# Thing_Plus_MGM240P.net
KiCad netlist of a schematic drawn in EAGLE
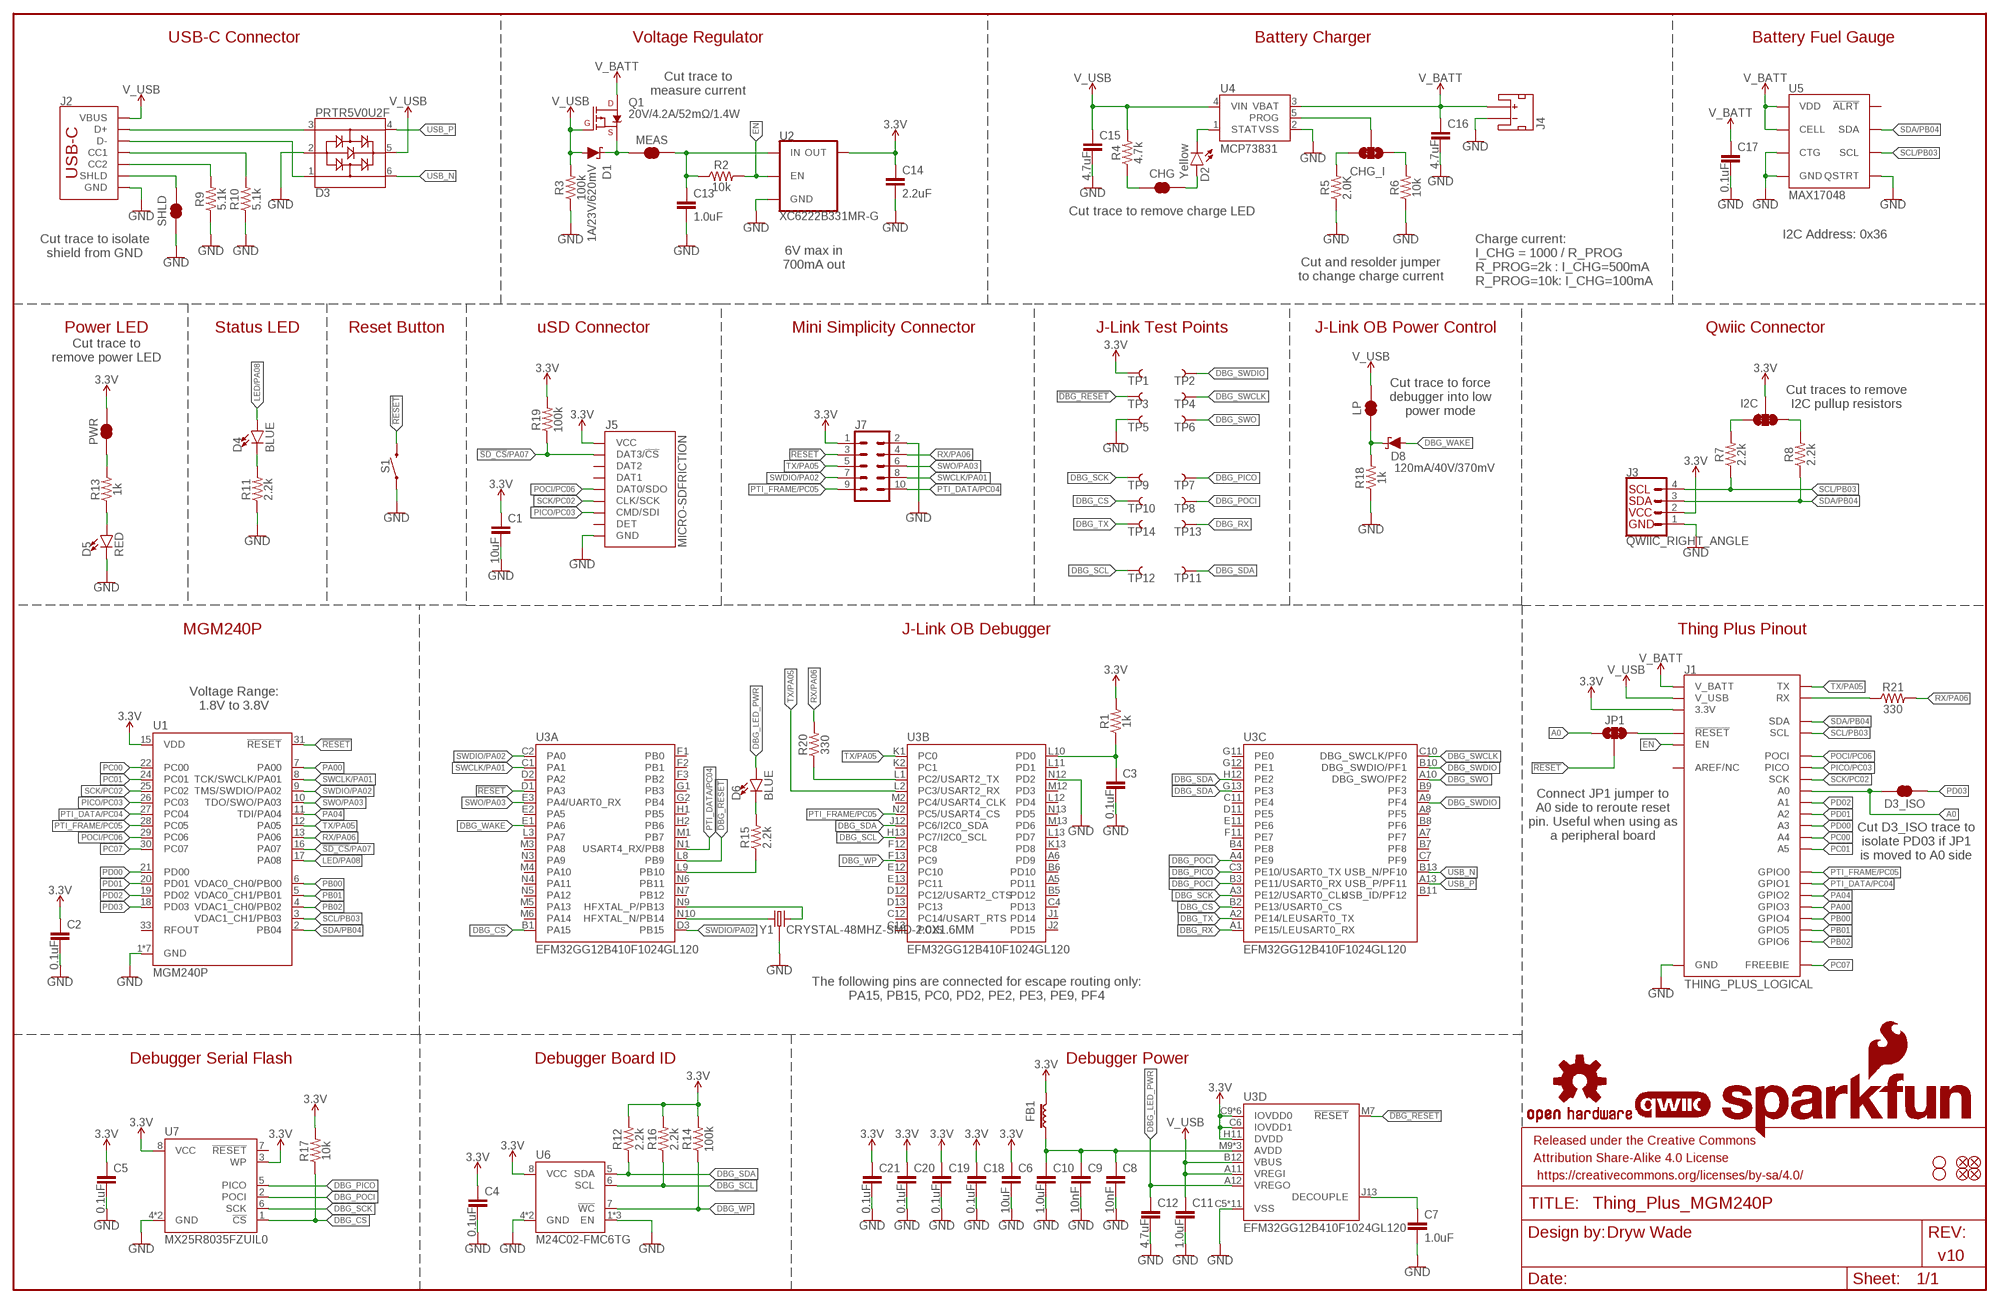
[diagram p0: schematic, sheet 1]

(export (version "E")
  (design (tool "Eeschema 10.0.6"))
  (components
    (comp (ref "C1")
      (value "10uF")
      (footprint "eagle-import:0402-TIGHT")
      (libsource (lib "eagle-import") (part "10UF-0402T-6.3V-20%"))
    )
    (comp (ref "C2")
      (value "0.1uF")
      (footprint "eagle-import:0402-TIGHT")
      (libsource (lib "eagle-import") (part "0.1UF-0402T-6.3V-10%-X7R"))
    )
    (comp (ref "C3")
      (value "0.1uF")
      (footprint "eagle-import:0402-TIGHT")
      (libsource (lib "eagle-import") (part "0.1UF-0402T-6.3V-10%-X7R"))
    )
    (comp (ref "C4")
      (value "0.1uF")
      (footprint "eagle-import:0402-TIGHT")
      (libsource (lib "eagle-import") (part "0.1UF-0402T-6.3V-10%-X7R"))
    )
    (comp (ref "C5")
      (value "0.1uF")
      (footprint "eagle-import:0402-TIGHT")
      (libsource (lib "eagle-import") (part "0.1UF-0402T-6.3V-10%-X7R"))
    )
    (comp (ref "C6")
      (value "10uF")
      (footprint "eagle-import:0402-TIGHT")
      (libsource (lib "eagle-import") (part "10UF-0402T-6.3V-20%"))
    )
    (comp (ref "C7")
      (value "1.0uF")
      (footprint "eagle-import:0603")
      (libsource (lib "eagle-import") (part "1.0UF-0603-16V-10%-X7R"))
    )
    (comp (ref "C8")
      (value "10nF")
      (footprint "eagle-import:0402-TIGHT")
      (libsource (lib "eagle-import") (part "10NF-0402T-25V-10%"))
    )
    (comp (ref "C9")
      (value "10nF")
      (footprint "eagle-import:0402-TIGHT")
      (libsource (lib "eagle-import") (part "10NF-0402T-25V-10%"))
    )
    (comp (ref "C10")
      (value "1.0uF")
      (footprint "eagle-import:0402-TIGHT")
      (libsource (lib "eagle-import") (part "1.0UF-0402T-16V-10%"))
    )
    (comp (ref "C11")
      (value "1.0uF")
      (footprint "eagle-import:0402-TIGHT")
      (libsource (lib "eagle-import") (part "1.0UF-0402T-16V-10%"))
    )
    (comp (ref "C12")
      (value "4.7uF")
      (footprint "eagle-import:0402-TIGHT")
      (libsource (lib "eagle-import") (part "4.7UF-0402_TIGHT-6.3V-20%-X5R"))
    )
    (comp (ref "C13")
      (value "1.0uF")
      (footprint "eagle-import:0402-TIGHT")
      (libsource (lib "eagle-import") (part "1.0UF-0402T-16V-10%"))
    )
    (comp (ref "C14")
      (value "2.2uF")
      (footprint "eagle-import:0402-TIGHT")
      (libsource (lib "eagle-import") (part "2.2UF-0402_TIGHT-10V-10%-X5R"))
    )
    (comp (ref "C15")
      (value "4.7uF")
      (footprint "eagle-import:0402-TIGHT")
      (libsource (lib "eagle-import") (part "4.7UF-0402_TIGHT-6.3V-20%-X5R"))
    )
    (comp (ref "C16")
      (value "4.7uF")
      (footprint "eagle-import:0402-TIGHT")
      (libsource (lib "eagle-import") (part "4.7UF-0402_TIGHT-6.3V-20%-X5R"))
    )
    (comp (ref "C17")
      (value "0.1uF")
      (footprint "eagle-import:0402-TIGHT")
      (libsource (lib "eagle-import") (part "0.1UF-0402T-6.3V-10%-X7R"))
    )
    (comp (ref "C18")
      (value "0.1uF")
      (footprint "eagle-import:0402-TIGHT")
      (libsource (lib "eagle-import") (part "0.1UF-0402T-6.3V-10%-X7R"))
    )
    (comp (ref "C19")
      (value "0.1uF")
      (footprint "eagle-import:0402-TIGHT")
      (libsource (lib "eagle-import") (part "0.1UF-0402T-6.3V-10%-X7R"))
    )
    (comp (ref "C20")
      (value "0.1uF")
      (footprint "eagle-import:0402-TIGHT")
      (libsource (lib "eagle-import") (part "0.1UF-0402T-6.3V-10%-X7R"))
    )
    (comp (ref "C21")
      (value "0.1uF")
      (footprint "eagle-import:0402-TIGHT")
      (libsource (lib "eagle-import") (part "0.1UF-0402T-6.3V-10%-X7R"))
    )
    (comp (ref "CHG")
      (value "JUMPER-SMT_2_NC_TRACE_SILK")
      (footprint "eagle-import:SMT-JUMPER_2_NC_TRACE_SILK")
      (libsource (lib "eagle-import") (part "JUMPER-SMT_2_NC_TRACE_SILK"))
    )
    (comp (ref "CHG_I")
      (value "JUMPER-SMT_3_1-NC_TRACE_SILK")
      (footprint "eagle-import:SMT-JUMPER_3_1-NC_TRACE_SILK")
      (libsource (lib "eagle-import") (part "JUMPER-SMT_3_1-NC_TRACE_SILK"))
    )
    (comp (ref "D1")
      (value "1A/23V/620mV")
      (footprint "eagle-import:SOD-323")
      (libsource (lib "eagle-import") (part "DIODE-SCHOTTKY-BAT20J"))
    )
    (comp (ref "D2")
      (value "Yellow")
      (footprint "eagle-import:LED-0603")
      (libsource (lib "eagle-import") (part "LED-YELLOW0603"))
    )
    (comp (ref "D3")
      (value "PRTR5V0U2F")
      (footprint "eagle-import:SOT886")
      (libsource (lib "eagle-import") (part "PRTR5V0U2F"))
    )
    (comp (ref "D3_ISO")
      (value "JUMPER-SMT_2_NC_TRACE_SILK")
      (footprint "eagle-import:SMT-JUMPER_2_NC_TRACE_SILK")
      (libsource (lib "eagle-import") (part "JUMPER-SMT_2_NC_TRACE_SILK"))
    )
    (comp (ref "D4")
      (value "BLUE")
      (footprint "eagle-import:LED-0603")
      (libsource (lib "eagle-import") (part "LED-BLUE0603"))
    )
    (comp (ref "D5")
      (value "RED")
      (footprint "eagle-import:LED-0603")
      (libsource (lib "eagle-import") (part "LED-RED0603"))
    )
    (comp (ref "D6")
      (value "BLUE")
      (footprint "eagle-import:LED-0603")
      (libsource (lib "eagle-import") (part "LED-BLUE0603"))
    )
    (comp (ref "D8")
      (value "120mA/40V/370mV")
      (footprint "eagle-import:SOD-523")
      (libsource (lib "eagle-import") (part "DIODE-SCHOTTKY-RB751S40"))
    )
    (comp (ref "FB1")
      (value "FERRITE_BEAD-120_OHM-0402T")
      (footprint "eagle-import:0402-TIGHT")
      (libsource (lib "eagle-import") (part "FERRITE_BEAD-120_OHM-0402T"))
    )
    (comp (ref "FD1")
      (value "FIDUCIAL1X2")
      (footprint "eagle-import:FIDUCIAL-1X2")
      (libsource (lib "eagle-import") (part "FIDUCIAL1X2"))
    )
    (comp (ref "FD2")
      (value "FIDUCIAL1X2")
      (footprint "eagle-import:FIDUCIAL-1X2")
      (libsource (lib "eagle-import") (part "FIDUCIAL1X2"))
    )
    (comp (ref "FD3")
      (value "FIDUCIAL1X2")
      (footprint "eagle-import:FIDUCIAL-1X2")
      (libsource (lib "eagle-import") (part "FIDUCIAL1X2"))
    )
    (comp (ref "FD4")
      (value "FIDUCIAL1X2")
      (footprint "eagle-import:FIDUCIAL-1X2")
      (libsource (lib "eagle-import") (part "FIDUCIAL1X2"))
    )
    (comp (ref "FRAME1")
      (value "FRAME-LEDGER")
      (footprint "eagle-import:CREATIVE_COMMONS")
      (libsource (lib "eagle-import") (part "FRAME-LEDGER"))
    )
    (comp (ref "H1")
      (value "STAND-OFF")
      (footprint "eagle-import:STAND-OFF")
      (libsource (lib "eagle-import") (part "STAND-OFF"))
    )
    (comp (ref "H2")
      (value "STAND-OFF")
      (footprint "eagle-import:STAND-OFF")
      (libsource (lib "eagle-import") (part "STAND-OFF"))
    )
    (comp (ref "I2C")
      (value "JUMPER-SMT_3_2-NC_TRACE_SILK")
      (footprint "eagle-import:SMT-JUMPER_3_2-NC_TRACE_SILK")
      (libsource (lib "eagle-import") (part "JUMPER-SMT_3_2-NC_TRACE_SILK"))
    )
    (comp (ref "J1")
      (value "THING_PLUS_LOGICAL")
      (footprint "eagle-import:THING_PLUS")
      (libsource (lib "eagle-import") (part "THING_PLUS_LOGICAL"))
    )
    (comp (ref "J2")
      (value "USB Female Type C Connector")
      (footprint "eagle-import:USB-C-16P-4LAYER-ISOLATED")
      (libsource (lib "eagle-import") (part "USB_C_4-LAYER-ISOLATED"))
    )
    (comp (ref "J3")
      (value "QWIIC_RIGHT_ANGLE")
      (footprint "eagle-import:JST04_1MM_RA")
      (libsource (lib "eagle-import") (part "QWIIC_CONNECTORJS-1MM"))
    )
    (comp (ref "J4")
      (value "JST_2MM_MALE")
      (footprint "eagle-import:JST-2-SMD")
      (libsource (lib "eagle-import") (part "JST_2MM_MALE"))
    )
    (comp (ref "J5")
      (value "MICRO-SDFRICTION")
      (footprint "eagle-import:MICROSD_TINY")
      (libsource (lib "eagle-import") (part "MICRO-SDFRICTION"))
    )
    (comp (ref "J7")
      (value "CONN_05X20.05_IN_PTH_SILK")
      (footprint "eagle-import:2X5_PTH_SILK_.05")
      (libsource (lib "eagle-import") (part "CONN_05X20.05_IN_PTH_SILK"))
    )
    (comp (ref "JP1")
      (value "JUMPER-SMT_3_1-NC_TRACE_SILK")
      (footprint "eagle-import:SMT-JUMPER_3_1-NC_TRACE_SILK")
      (libsource (lib "eagle-import") (part "JUMPER-SMT_3_1-NC_TRACE_SILK"))
    )
    (comp (ref "LOGO1")
      (value "SFE_LOGO_NAME_FLAME.1_INCH")
      (footprint "eagle-import:SFE_LOGO_NAME_FLAME_.1")
      (libsource (lib "eagle-import") (part "SFE_LOGO_NAME_FLAME.1_INCH"))
    )
    (comp (ref "LOGO2")
      (value "QWIIC_LOGO_3MM")
      (footprint "eagle-import:QWIIC_3MM")
      (libsource (lib "eagle-import") (part "QWIIC_LOGO_3MM"))
    )
    (comp (ref "LOGO3")
      (value "OSHW-LOGOS")
      (footprint "eagle-import:OSHW-LOGO-S")
      (libsource (lib "eagle-import") (part "OSHW-LOGOS"))
    )
    (comp (ref "LP")
      (value "JUMPER-SMT_2_NC_TRACE_SILK")
      (footprint "eagle-import:SMT-JUMPER_2_NC_TRACE_SILK")
      (libsource (lib "eagle-import") (part "JUMPER-SMT_2_NC_TRACE_SILK"))
    )
    (comp (ref "MEAS")
      (value "JUMPER-COMBO_2_NC_TRACE")
      (footprint "eagle-import:COMBO-JUMPER_2_NC_TRACE")
      (libsource (lib "eagle-import") (part "JUMPER-COMBO_2_NC_TRACE"))
    )
    (comp (ref "PWR")
      (value "JUMPER-SMT_2_NC_TRACE_SILK")
      (footprint "eagle-import:SMT-JUMPER_2_NC_TRACE_SILK")
      (libsource (lib "eagle-import") (part "JUMPER-SMT_2_NC_TRACE_SILK"))
    )
    (comp (ref "Q1")
      (value "20V/4.2A/52mΩ/1.4W")
      (footprint "eagle-import:SOT23-3")
      (libsource (lib "eagle-import") (part "MOSFET_PCH-DMG2305UX-7"))
    )
    (comp (ref "R1")
      (value "1k")
      (footprint "eagle-import:0402-TIGHT")
      (libsource (lib "eagle-import") (part "1KOHM-0402T-1/16W-1%"))
    )
    (comp (ref "R2")
      (value "10k")
      (footprint "eagle-import:0402-TIGHT")
      (libsource (lib "eagle-import") (part "10KOHM-0402T-1/16W-1%"))
    )
    (comp (ref "R3")
      (value "100k")
      (footprint "eagle-import:0402-TIGHT")
      (libsource (lib "eagle-import") (part "100KOHM-0402T-1/16W-1%"))
    )
    (comp (ref "R4")
      (value "4.7k")
      (footprint "eagle-import:0402-TIGHT")
      (libsource (lib "eagle-import") (part "4.7KOHM-0402T-1/16W-1%"))
    )
    (comp (ref "R5")
      (value "2.0K")
      (footprint "eagle-import:0402-TIGHT")
      (libsource (lib "eagle-import") (part "2.0KOHM-0402T-1/16W-1%"))
    )
    (comp (ref "R6")
      (value "10k")
      (footprint "eagle-import:0402-TIGHT")
      (libsource (lib "eagle-import") (part "10KOHM-0402T-1/16W-1%"))
    )
    (comp (ref "R7")
      (value "2.2k")
      (footprint "eagle-import:0402-TIGHT")
      (libsource (lib "eagle-import") (part "2.2KOHM-0402T-1/16W-1%"))
    )
    (comp (ref "R8")
      (value "2.2k")
      (footprint "eagle-import:0402-TIGHT")
      (libsource (lib "eagle-import") (part "2.2KOHM-0402T-1/16W-1%"))
    )
    (comp (ref "R9")
      (value "5.1k")
      (footprint "eagle-import:0402-TIGHT")
      (libsource (lib "eagle-import") (part "5.1KOHM-0402T-1/16W-1%"))
    )
    (comp (ref "R10")
      (value "5.1k")
      (footprint "eagle-import:0402-TIGHT")
      (libsource (lib "eagle-import") (part "5.1KOHM-0402T-1/16W-1%"))
    )
    (comp (ref "R11")
      (value "2.2k")
      (footprint "eagle-import:0402-TIGHT")
      (libsource (lib "eagle-import") (part "2.2KOHM-0402T-1/16W-1%"))
    )
    (comp (ref "R12")
      (value "2.2k")
      (footprint "eagle-import:0402-TIGHT")
      (libsource (lib "eagle-import") (part "2.2KOHM-0402T-1/16W-1%"))
    )
    (comp (ref "R13")
      (value "1k")
      (footprint "eagle-import:0402-TIGHT")
      (libsource (lib "eagle-import") (part "1KOHM-0402T-1/16W-1%"))
    )
    (comp (ref "R14")
      (value "100k")
      (footprint "eagle-import:0402-TIGHT")
      (libsource (lib "eagle-import") (part "100KOHM-0402T-1/16W-1%"))
    )
    (comp (ref "R15")
      (value "2.2k")
      (footprint "eagle-import:0402-TIGHT")
      (libsource (lib "eagle-import") (part "2.2KOHM-0402T-1/16W-1%"))
    )
    (comp (ref "R16")
      (value "2.2k")
      (footprint "eagle-import:0402-TIGHT")
      (libsource (lib "eagle-import") (part "2.2KOHM-0402T-1/16W-1%"))
    )
    (comp (ref "R17")
      (value "10k")
      (footprint "eagle-import:0402-TIGHT")
      (libsource (lib "eagle-import") (part "10KOHM-0402T-1/16W-1%"))
    )
    (comp (ref "R18")
      (value "1k")
      (footprint "eagle-import:0402-TIGHT")
      (libsource (lib "eagle-import") (part "1KOHM-0402T-1/16W-1%"))
    )
    (comp (ref "R19")
      (value "100k")
      (footprint "eagle-import:0402-TIGHT")
      (libsource (lib "eagle-import") (part "100KOHM-0402T-1/16W-1%"))
    )
    (comp (ref "R20")
      (value "330")
      (footprint "eagle-import:0402-TIGHT")
      (libsource (lib "eagle-import") (part "330OHM-0402T-1/16W-5%"))
    )
    (comp (ref "R21")
      (value "330")
      (footprint "eagle-import:0402-TIGHT")
      (libsource (lib "eagle-import") (part "330OHM-0402T-1/16W-5%"))
    )
    (comp (ref "S1")
      (value "MOMENTARY-SWITCH-SPST-SMD-4.6X2.8MM")
      (footprint "eagle-import:TACTILE_SWITCH_SMD_4.6X2.8MM")
      (libsource (lib "eagle-import") (part "MOMENTARY-SWITCH-SPST-SMD-4.6X2.8MM"))
    )
    (comp (ref "SHLD")
      (value "JUMPER-SMT_2_NC_TRACE_SILK")
      (footprint "eagle-import:SMT-JUMPER_2_NC_TRACE_SILK")
      (libsource (lib "eagle-import") (part "JUMPER-SMT_2_NC_TRACE_SILK"))
    )
    (comp (ref "TP1")
      (value "TEST-POINT3")
      (footprint "eagle-import:PAD.03X.03")
      (libsource (lib "eagle-import") (part "TEST-POINT3"))
    )
    (comp (ref "TP2")
      (value "TEST-POINT3")
      (footprint "eagle-import:PAD.03X.03")
      (libsource (lib "eagle-import") (part "TEST-POINT3"))
    )
    (comp (ref "TP3")
      (value "TEST-POINT3")
      (footprint "eagle-import:PAD.03X.03")
      (libsource (lib "eagle-import") (part "TEST-POINT3"))
    )
    (comp (ref "TP4")
      (value "TEST-POINT3")
      (footprint "eagle-import:PAD.03X.03")
      (libsource (lib "eagle-import") (part "TEST-POINT3"))
    )
    (comp (ref "TP5")
      (value "TEST-POINT3")
      (footprint "eagle-import:PAD.03X.03")
      (libsource (lib "eagle-import") (part "TEST-POINT3"))
    )
    (comp (ref "TP6")
      (value "TEST-POINT3")
      (footprint "eagle-import:PAD.03X.03")
      (libsource (lib "eagle-import") (part "TEST-POINT3"))
    )
    (comp (ref "TP7")
      (value "TEST-POINT3")
      (footprint "eagle-import:PAD.03X.03")
      (libsource (lib "eagle-import") (part "TEST-POINT3"))
    )
    (comp (ref "TP8")
      (value "TEST-POINT3")
      (footprint "eagle-import:PAD.03X.03")
      (libsource (lib "eagle-import") (part "TEST-POINT3"))
    )
    (comp (ref "TP9")
      (value "TEST-POINT3")
      (footprint "eagle-import:PAD.03X.03")
      (libsource (lib "eagle-import") (part "TEST-POINT3"))
    )
    (comp (ref "TP10")
      (value "TEST-POINT3")
      (footprint "eagle-import:PAD.03X.03")
      (libsource (lib "eagle-import") (part "TEST-POINT3"))
    )
    (comp (ref "TP11")
      (value "TEST-POINT3")
      (footprint "eagle-import:PAD.03X.03")
      (libsource (lib "eagle-import") (part "TEST-POINT3"))
    )
    (comp (ref "TP12")
      (value "TEST-POINT3")
      (footprint "eagle-import:PAD.03X.03")
      (libsource (lib "eagle-import") (part "TEST-POINT3"))
    )
    (comp (ref "TP13")
      (value "TEST-POINT3")
      (footprint "eagle-import:PAD.03X.03")
      (libsource (lib "eagle-import") (part "TEST-POINT3"))
    )
    (comp (ref "TP14")
      (value "TEST-POINT3")
      (footprint "eagle-import:PAD.03X.03")
      (libsource (lib "eagle-import") (part "TEST-POINT3"))
    )
    (comp (ref "U1")
      (value "MGM240P")
      (footprint "eagle-import:MGM240P")
      (libsource (lib "eagle-import") (part "MGM240P"))
    )
    (comp (ref "U2")
      (value "XC6222B331MR-G")
      (footprint "eagle-import:SOT23-5")
      (libsource (lib "eagle-import") (part "XC6222B331MR-G"))
    )
    (comp (ref "U3")
      (value "EFM32GG12B410F1024GL120")
      (footprint "eagle-import:BGA120")
      (libsource (lib "eagle-import") (part "EFM32GG12B410F1024GL120"))
    )
    (comp (ref "U4")
      (value "MCP73831")
      (footprint "eagle-import:SOT23-5")
      (libsource (lib "eagle-import") (part "MCP73831"))
    )
    (comp (ref "U5")
      (value "MAX17048")
      (footprint "eagle-import:DFN-8")
      (libsource (lib "eagle-import") (part "MAX17048DFN8"))
    )
    (comp (ref "U6")
      (value "M24C02-FMC6TG")
      (footprint "eagle-import:DFN8_2X3MM")
      (libsource (lib "eagle-import") (part "M24C02-FMC6TG"))
    )
    (comp (ref "U7")
      (value "MX25R8035FZUIL0")
      (footprint "eagle-import:USON-8_2X3MM")
      (libsource (lib "eagle-import") (part "MX25R8035FZUIL0"))
    )
    (comp (ref "Y1")
      (value "CRYSTAL-48MHZ-SMD-2.0X1.6MM")
      (footprint "eagle-import:CRYSTAL-SMD-2.0X1.6MM-ECS")
      (libsource (lib "eagle-import") (part "CRYSTAL-48MHZ-SMD-2.0X1.6MM"))
    )
  )
  (nets
    (net (code "1") (name "/~{DBG_RESET}") (class "Default")
      (node (ref "TP3") (pin "1") (pinfunction "1_1") (pintype "bidirectional"))
      (node (ref "U3") (pin "L8") (pinfunction "PB9_L8") (pintype "bidirectional"))
      (node (ref "U3") (pin "M7") (pinfunction "~{RESET}_M7") (pintype "bidirectional"))
    )
    (net (code "2") (name "/~{RESET}") (class "Default")
      (node (ref "J7") (pin "3") (pinfunction "3_3") (pintype "passive"))
      (node (ref "JP1") (pin "2") (pinfunction "2_2") (pintype "passive"))
      (node (ref "S1") (pin "3") (pinfunction "2_3") (pintype "passive"))
      (node (ref "S1") (pin "4") (pinfunction "2_4") (pintype "passive"))
      (node (ref "U1") (pin "31") (pinfunction "~{RESET}_31") (pintype "input"))
      (node (ref "U3") (pin "D1") (pinfunction "PA3_D1") (pintype "bidirectional"))
    )
    (net (code "3") (name "/~{SD_CS}{slash}PA07") (class "Default")
      (node (ref "J5") (pin "2") (pinfunction "DAT3/~{CS}_2") (pintype "bidirectional"))
      (node (ref "R19") (pin "1") (pinfunction "1_1") (pintype "passive"))
      (node (ref "U1") (pin "16") (pinfunction "PA07_16") (pintype "bidirectional"))
    )
    (net (code "4") (name "3.3V") (class "Default")
      (node (ref "C1") (pin "1") (pinfunction "1_1") (pintype "passive"))
      (node (ref "C14") (pin "1") (pinfunction "1_1") (pintype "passive"))
      (node (ref "C18") (pin "1") (pinfunction "1_1") (pintype "passive"))
      (node (ref "C19") (pin "1") (pinfunction "1_1") (pintype "passive"))
      (node (ref "C2") (pin "1") (pinfunction "1_1") (pintype "passive"))
      (node (ref "C20") (pin "1") (pinfunction "1_1") (pintype "passive"))
      (node (ref "C21") (pin "1") (pinfunction "1_1") (pintype "passive"))
      (node (ref "C4") (pin "1") (pinfunction "1_1") (pintype "passive"))
      (node (ref "C5") (pin "1") (pinfunction "1_1") (pintype "passive"))
      (node (ref "C6") (pin "1") (pinfunction "1_1") (pintype "passive"))
      (node (ref "FB1") (pin "2") (pinfunction "2_2") (pintype "passive"))
      (node (ref "I2C") (pin "2") (pinfunction "2_2") (pintype "passive"))
      (node (ref "J1") (pin "27") (pinfunction "3.3V_27") (pintype "bidirectional"))
      (node (ref "J3") (pin "2") (pinfunction "2_2") (pintype "power_in"))
      (node (ref "J5") (pin "4") (pinfunction "VCC_4") (pintype "bidirectional"))
      (node (ref "J7") (pin "1") (pinfunction "1_1") (pintype "passive"))
      (node (ref "PWR") (pin "2") (pinfunction "2_2") (pintype "passive"))
      (node (ref "R1") (pin "2") (pinfunction "2_2") (pintype "passive"))
      (node (ref "R12") (pin "2") (pinfunction "2_2") (pintype "passive"))
      (node (ref "R14") (pin "2") (pinfunction "2_2") (pintype "passive"))
      (node (ref "R16") (pin "2") (pinfunction "2_2") (pintype "passive"))
      (node (ref "R17") (pin "2") (pinfunction "2_2") (pintype "passive"))
      (node (ref "R19") (pin "2") (pinfunction "2_2") (pintype "passive"))
      (node (ref "TP1") (pin "1") (pinfunction "1_1") (pintype "bidirectional"))
      (node (ref "U1") (pin "15") (pinfunction "VDD_15") (pintype "power_in"))
      (node (ref "U2") (pin "5") (pinfunction "OUT_5") (pintype "passive"))
      (node (ref "U3") (pin "C6") (pinfunction "IOVDD1_C6") (pintype "bidirectional"))
      (node (ref "U3") (pin "C9") (pinfunction "IOVDD0_C9") (pintype "bidirectional"))
      (node (ref "U3") (pin "G3") (pinfunction "IOVDD0_G3") (pintype "bidirectional"))
      (node (ref "U3") (pin "H11") (pinfunction "DVDD_H11") (pintype "bidirectional"))
      (node (ref "U3") (pin "J11") (pinfunction "IOVDD0_J11") (pintype "bidirectional"))
      (node (ref "U3") (pin "K3") (pinfunction "IOVDD0_K3") (pintype "bidirectional"))
      (node (ref "U3") (pin "L4") (pinfunction "IOVDD0_L4") (pintype "bidirectional"))
      (node (ref "U3") (pin "L7") (pinfunction "IOVDD0_L7") (pintype "bidirectional"))
      (node (ref "U6") (pin "8") (pinfunction "VCC_8") (pintype "bidirectional"))
      (node (ref "U7") (pin "3") (pinfunction "WP_3") (pintype "bidirectional"))
      (node (ref "U7") (pin "8") (pinfunction "VCC_8") (pintype "bidirectional"))
    )
    (net (code "5") (name "A0") (class "Default")
      (node (ref "D3_ISO") (pin "2") (pinfunction "2_2") (pintype "passive"))
      (node (ref "J1") (pin "24") (pinfunction "A0_24") (pintype "bidirectional"))
      (node (ref "JP1") (pin "1") (pinfunction "1_1") (pintype "passive"))
    )
    (net (code "6") (name "DBG_CS") (class "Default")
      (node (ref "R17") (pin "1") (pinfunction "1_1") (pintype "passive"))
      (node (ref "TP10") (pin "1") (pinfunction "1_1") (pintype "bidirectional"))
      (node (ref "U3") (pin "B1") (pinfunction "PA15_B1") (pintype "bidirectional"))
      (node (ref "U3") (pin "B2") (pinfunction "PE13/USART0_CS_B2") (pintype "bidirectional"))
      (node (ref "U7") (pin "1") (pinfunction "~{CS}_1") (pintype "bidirectional"))
    )
    (net (code "7") (name "DBG_LED_PWR") (class "Default")
      (node (ref "C12") (pin "1") (pinfunction "1_1") (pintype "passive"))
      (node (ref "D6") (pin "A") (pinfunction "A_A") (pintype "passive"))
      (node (ref "U3") (pin "A12") (pinfunction "VREGO_A12") (pintype "bidirectional"))
    )
    (net (code "8") (name "DBG_PICO") (class "Default")
      (node (ref "TP7") (pin "1") (pinfunction "1_1") (pintype "bidirectional"))
      (node (ref "U3") (pin "C3") (pinfunction "PE10/USART0_TX_C3") (pintype "bidirectional"))
      (node (ref "U7") (pin "5") (pinfunction "PICO_5") (pintype "bidirectional"))
    )
    (net (code "9") (name "DBG_POCI") (class "Default")
      (node (ref "TP8") (pin "1") (pinfunction "1_1") (pintype "bidirectional"))
      (node (ref "U3") (pin "A4") (pinfunction "PE9_A4") (pintype "bidirectional"))
      (node (ref "U3") (pin "B3") (pinfunction "PE11/USART0_RX_B3") (pintype "bidirectional"))
      (node (ref "U7") (pin "2") (pinfunction "POCI_2") (pintype "bidirectional"))
    )
    (net (code "10") (name "DBG_RX") (class "Default")
      (node (ref "TP13") (pin "1") (pinfunction "1_1") (pintype "bidirectional"))
      (node (ref "U3") (pin "A1") (pinfunction "PE15/LEUSART0_RX_A1") (pintype "bidirectional"))
    )
    (net (code "11") (name "DBG_SCK") (class "Default")
      (node (ref "TP9") (pin "1") (pinfunction "1_1") (pintype "bidirectional"))
      (node (ref "U3") (pin "A3") (pinfunction "PE12/USART0_CLK_A3") (pintype "bidirectional"))
      (node (ref "U7") (pin "6") (pinfunction "SCK_6") (pintype "bidirectional"))
    )
    (net (code "12") (name "DBG_SCL") (class "Default")
      (node (ref "R16") (pin "1") (pinfunction "1_1") (pintype "passive"))
      (node (ref "TP12") (pin "1") (pinfunction "1_1") (pintype "bidirectional"))
      (node (ref "U3") (pin "H13") (pinfunction "PC7/I2C0_SCL_H13") (pintype "bidirectional"))
      (node (ref "U6") (pin "6") (pinfunction "SCL_6") (pintype "bidirectional"))
    )
    (net (code "13") (name "DBG_SDA") (class "Default")
      (node (ref "R12") (pin "1") (pinfunction "1_1") (pintype "passive"))
      (node (ref "TP11") (pin "1") (pinfunction "1_1") (pintype "bidirectional"))
      (node (ref "U3") (pin "G13") (pinfunction "PE3_G13") (pintype "bidirectional"))
      (node (ref "U3") (pin "H12") (pinfunction "PE2_H12") (pintype "bidirectional"))
      (node (ref "U3") (pin "J12") (pinfunction "PC6/I2C0_SDA_J12") (pintype "bidirectional"))
      (node (ref "U6") (pin "5") (pinfunction "SDA_5") (pintype "bidirectional"))
    )
    (net (code "14") (name "DBG_SWCLK") (class "Default")
      (node (ref "TP4") (pin "1") (pinfunction "1_1") (pintype "bidirectional"))
      (node (ref "U3") (pin "C10") (pinfunction "DBG_SWCLK/PF0_C10") (pintype "bidirectional"))
    )
    (net (code "15") (name "DBG_SWDIO") (class "Default")
      (node (ref "TP2") (pin "1") (pinfunction "1_1") (pintype "bidirectional"))
      (node (ref "U3") (pin "A9") (pinfunction "PF4_A9") (pintype "bidirectional"))
      (node (ref "U3") (pin "B10") (pinfunction "DBG_SWDIO/PF1_B10") (pintype "bidirectional"))
    )
    (net (code "16") (name "DBG_SWO") (class "Default")
      (node (ref "TP6") (pin "1") (pinfunction "1_1") (pintype "bidirectional"))
      (node (ref "U3") (pin "A10") (pinfunction "DBG_SWO/PF2_A10") (pintype "bidirectional"))
    )
    (net (code "17") (name "DBG_TX") (class "Default")
      (node (ref "TP14") (pin "1") (pinfunction "1_1") (pintype "bidirectional"))
      (node (ref "U3") (pin "A2") (pinfunction "PE14/LEUSART0_TX_A2") (pintype "bidirectional"))
    )
    (net (code "18") (name "DBG_WAKE") (class "Default")
      (node (ref "D8") (pin "A") (pinfunction "A_A") (pintype "passive"))
      (node (ref "U3") (pin "E1") (pinfunction "PA6_E1") (pintype "bidirectional"))
    )
    (net (code "19") (name "DBG_WP") (class "Default")
      (node (ref "R14") (pin "1") (pinfunction "1_1") (pintype "passive"))
      (node (ref "U3") (pin "F13") (pinfunction "PC9_F13") (pintype "bidirectional"))
      (node (ref "U6") (pin "7") (pinfunction "~{WC}_7") (pintype "bidirectional"))
    )
    (net (code "20") (name "EN") (class "Default")
      (node (ref "J1") (pin "11") (pinfunction "EN_11") (pintype "bidirectional"))
      (node (ref "R2") (pin "2") (pinfunction "2_2") (pintype "passive"))
      (node (ref "U2") (pin "3") (pinfunction "EN_3") (pintype "input"))
    )
    (net (code "21") (name "GND") (class "Default")
      (node (ref "C1") (pin "2") (pinfunction "2_2") (pintype "passive"))
      (node (ref "C10") (pin "2") (pinfunction "2_2") (pintype "passive"))
      (node (ref "C11") (pin "2") (pinfunction "2_2") (pintype "passive"))
      (node (ref "C12") (pin "2") (pinfunction "2_2") (pintype "passive"))
      (node (ref "C13") (pin "2") (pinfunction "2_2") (pintype "passive"))
      (node (ref "C14") (pin "2") (pinfunction "2_2") (pintype "passive"))
      (node (ref "C15") (pin "2") (pinfunction "2_2") (pintype "passive"))
      (node (ref "C16") (pin "2") (pinfunction "2_2") (pintype "passive"))
      (node (ref "C17") (pin "2") (pinfunction "2_2") (pintype "passive"))
      (node (ref "C18") (pin "2") (pinfunction "2_2") (pintype "passive"))
      (node (ref "C19") (pin "2") (pinfunction "2_2") (pintype "passive"))
      (node (ref "C2") (pin "2") (pinfunction "2_2") (pintype "passive"))
      (node (ref "C20") (pin "2") (pinfunction "2_2") (pintype "passive"))
      (node (ref "C21") (pin "2") (pinfunction "2_2") (pintype "passive"))
      (node (ref "C3") (pin "2") (pinfunction "2_2") (pintype "passive"))
      (node (ref "C4") (pin "2") (pinfunction "2_2") (pintype "passive"))
      (node (ref "C5") (pin "2") (pinfunction "2_2") (pintype "passive"))
      (node (ref "C6") (pin "2") (pinfunction "2_2") (pintype "passive"))
      (node (ref "C7") (pin "2") (pinfunction "2_2") (pintype "passive"))
      (node (ref "C8") (pin "2") (pinfunction "2_2") (pintype "passive"))
      (node (ref "C9") (pin "2") (pinfunction "2_2") (pintype "passive"))
      (node (ref "D3") (pin "2") (pinfunction "2_2") (pintype "power_in"))
      (node (ref "D5") (pin "C") (pinfunction "C_C") (pintype "passive"))
      (node (ref "J1") (pin "25") (pinfunction "GND_25") (pintype "bidirectional"))
      (node (ref "J2") (pin "GND") (pinfunction "GND_GND") (pintype "bidirectional"))
      (node (ref "J2") (pin "GND2") (pinfunction "GND_GND2") (pintype "bidirectional"))
      (node (ref "J3") (pin "1") (pinfunction "1_1") (pintype "power_in"))
      (node (ref "J4") (pin "1") (pinfunction "-_1") (pintype "bidirectional"))
      (node (ref "J5") (pin "6") (pinfunction "GND_6") (pintype "bidirectional"))
      (node (ref "J5") (pin "GND1") (pinfunction "GND_GND1") (pintype "bidirectional"))
      (node (ref "J5") (pin "GND2") (pinfunction "GND_GND2") (pintype "bidirectional"))
      (node (ref "J5") (pin "GND3") (pinfunction "GND_GND3") (pintype "bidirectional"))
      (node (ref "J5") (pin "GND4") (pinfunction "GND_GND4") (pintype "bidirectional"))
      (node (ref "J5") (pin "GND5") (pinfunction "GND_GND5") (pintype "bidirectional"))
      (node (ref "J5") (pin "GND6") (pinfunction "GND_GND6") (pintype "bidirectional"))
      (node (ref "J7") (pin "2") (pinfunction "2_2") (pintype "passive"))
      (node (ref "R10") (pin "1") (pinfunction "1_1") (pintype "passive"))
      (node (ref "R11") (pin "1") (pinfunction "1_1") (pintype "passive"))
      (node (ref "R18") (pin "1") (pinfunction "1_1") (pintype "passive"))
      (node (ref "R3") (pin "1") (pinfunction "1_1") (pintype "passive"))
      (node (ref "R5") (pin "1") (pinfunction "1_1") (pintype "passive"))
      (node (ref "R6") (pin "1") (pinfunction "1_1") (pintype "passive"))
      (node (ref "R9") (pin "1") (pinfunction "1_1") (pintype "passive"))
      (node (ref "S1") (pin "1") (pinfunction "1_1") (pintype "passive"))
      (node (ref "S1") (pin "2") (pinfunction "1_2") (pintype "passive"))
      (node (ref "SHLD") (pin "1") (pinfunction "1_1") (pintype "passive"))
      (node (ref "TP5") (pin "1") (pinfunction "1_1") (pintype "bidirectional"))
      (node (ref "U1") (pin "1") (pinfunction "GND_1") (pintype "power_in"))
      (node (ref "U1") (pin "14") (pinfunction "GND_14") (pintype "power_in"))
      (node (ref "U1") (pin "23") (pinfunction "GND_23") (pintype "power_in"))
      (node (ref "U1") (pin "32") (pinfunction "GND_32") (pintype "power_in"))
      (node (ref "U1") (pin "34") (pinfunction "GND_34") (pintype "power_in"))
      (node (ref "U1") (pin "35") (pinfunction "GND_35") (pintype "power_in"))
      (node (ref "U1") (pin "36") (pinfunction "GND_36") (pintype "power_in"))
      (node (ref "U2") (pin "2") (pinfunction "GND_2") (pintype "input"))
      (node (ref "U3") (pin "C5") (pinfunction "VSS_C5") (pintype "bidirectional"))
      (node (ref "U3") (pin "C8") (pinfunction "VSS_C8") (pintype "bidirectional"))
      (node (ref "U3") (pin "H3") (pinfunction "VSS_H3") (pintype "bidirectional"))
      (node (ref "U3") (pin "J3") (pinfunction "VSS_J3") (pintype "bidirectional"))
      (node (ref "U3") (pin "K11") (pinfunction "VSS_K11") (pintype "bidirectional"))
      (node (ref "U3") (pin "K12") (pinfunction "VSS_K12") (pintype "bidirectional"))
      (node (ref "U3") (pin "L5") (pinfunction "VSS_L5") (pintype "bidirectional"))
      (node (ref "U3") (pin "L6") (pinfunction "VSS_L6") (pintype "bidirectional"))
      (node (ref "U3") (pin "M11") (pinfunction "VSS_M11") (pintype "bidirectional"))
      (node (ref "U3") (pin "M8") (pinfunction "VSS_M8") (pintype "bidirectional"))
      (node (ref "U3") (pin "N12") (pinfunction "PD2_N12") (pintype "bidirectional"))
      (node (ref "U3") (pin "N8") (pinfunction "VSS_N8") (pintype "bidirectional"))
      (node (ref "U4") (pin "2") (pinfunction "VSS_2") (pintype "power_in"))
      (node (ref "U5") (pin "1") (pinfunction "CTG_1") (pintype "input"))
      (node (ref "U5") (pin "4") (pinfunction "GND_4") (pintype "bidirectional"))
      (node (ref "U5") (pin "6") (pinfunction "QSTRT_6") (pintype "bidirectional"))
      (node (ref "U5") (pin "9") (pinfunction "GND_9") (pintype "bidirectional"))
      (node (ref "U6") (pin "1") (pinfunction "EN_1") (pintype "bidirectional"))
      (node (ref "U6") (pin "2") (pinfunction "EN_2") (pintype "bidirectional"))
      (node (ref "U6") (pin "3") (pinfunction "EN_3") (pintype "bidirectional"))
      (node (ref "U6") (pin "4") (pinfunction "GND_4") (pintype "bidirectional"))
      (node (ref "U6") (pin "EPAD") (pinfunction "GND_EPAD") (pintype "bidirectional"))
      (node (ref "U7") (pin "4") (pinfunction "GND_4") (pintype "bidirectional"))
      (node (ref "U7") (pin "EPAD") (pinfunction "GND_EPAD") (pintype "bidirectional"))
      (node (ref "Y1") (pin "2") (pinfunction "GND_2") (pintype "power_in"))
      (node (ref "Y1") (pin "4") (pinfunction "GND_4") (pintype "power_in"))
    )
    (net (code "22") (name "LED{slash}PA08") (class "Default")
      (node (ref "D4") (pin "A") (pinfunction "A_A") (pintype "passive"))
      (node (ref "U1") (pin "17") (pinfunction "PA08_17") (pintype "bidirectional"))
    )
    (net (code "23") (name "Net-(C10-Pad1)") (class "Default")
      (node (ref "C10") (pin "1") (pinfunction "1_1") (pintype "passive"))
      (node (ref "C8") (pin "1") (pinfunction "1_1") (pintype "passive"))
      (node (ref "C9") (pin "1") (pinfunction "1_1") (pintype "passive"))
      (node (ref "FB1") (pin "1") (pinfunction "1_1") (pintype "passive"))
      (node (ref "U3") (pin "M10") (pinfunction "AVDD_M10") (pintype "bidirectional"))
      (node (ref "U3") (pin "M9") (pinfunction "AVDD_M9") (pintype "bidirectional"))
      (node (ref "U3") (pin "N11") (pinfunction "AVDD_N11") (pintype "bidirectional"))
    )
    (net (code "24") (name "Net-(CHG-Pad1)") (class "Default")
      (node (ref "CHG") (pin "1") (pinfunction "1_1") (pintype "passive"))
      (node (ref "R4") (pin "1") (pinfunction "1_1") (pintype "passive"))
    )
    (net (code "25") (name "Net-(CHG-Pad2)") (class "Default")
      (node (ref "CHG") (pin "2") (pinfunction "2_2") (pintype "passive"))
      (node (ref "D2") (pin "A") (pinfunction "A_A") (pintype "passive"))
    )
    (net (code "26") (name "Net-(CHG_I-Pad1)") (class "Default")
      (node (ref "CHG_I") (pin "1") (pinfunction "1_1") (pintype "passive"))
      (node (ref "R6") (pin "2") (pinfunction "2_2") (pintype "passive"))
    )
    (net (code "27") (name "Net-(CHG_I-Pad3)") (class "Default")
      (node (ref "CHG_I") (pin "3") (pinfunction "3_3") (pintype "passive"))
      (node (ref "R5") (pin "2") (pinfunction "2_2") (pintype "passive"))
    )
    (net (code "28") (name "Net-(D3-Pad1)") (class "Default")
      (node (ref "D3") (pin "1") (pinfunction "1_1") (pintype "bidirectional"))
      (node (ref "J2") (pin "A7") (pinfunction "D-_A7") (pintype "bidirectional"))
      (node (ref "J2") (pin "B7") (pinfunction "D-_B7") (pintype "bidirectional"))
    )
    (net (code "29") (name "Net-(D3-Pad3)") (class "Default")
      (node (ref "D3") (pin "3") (pinfunction "3_3") (pintype "bidirectional"))
      (node (ref "J2") (pin "A6") (pinfunction "D+_A6") (pintype "bidirectional"))
      (node (ref "J2") (pin "B6") (pinfunction "D+_B6") (pintype "bidirectional"))
    )
    (net (code "30") (name "Net-(D4-PadC)") (class "Default")
      (node (ref "D4") (pin "C") (pinfunction "C_C") (pintype "passive"))
      (node (ref "R11") (pin "2") (pinfunction "2_2") (pintype "passive"))
    )
    (net (code "31") (name "Net-(D5-PadA)") (class "Default")
      (node (ref "D5") (pin "A") (pinfunction "A_A") (pintype "passive"))
      (node (ref "R13") (pin "1") (pinfunction "1_1") (pintype "passive"))
    )
    (net (code "32") (name "Net-(D6-PadC)") (class "Default")
      (node (ref "D6") (pin "C") (pinfunction "C_C") (pintype "passive"))
      (node (ref "R15") (pin "2") (pinfunction "2_2") (pintype "passive"))
    )
    (net (code "33") (name "Net-(D8-PadC)") (class "Default")
      (node (ref "D8") (pin "C") (pinfunction "C_C") (pintype "passive"))
      (node (ref "LP") (pin "1") (pinfunction "1_1") (pintype "passive"))
      (node (ref "R18") (pin "2") (pinfunction "2_2") (pintype "passive"))
    )
    (net (code "34") (name "Net-(I2C-Pad1)") (class "Default")
      (node (ref "I2C") (pin "1") (pinfunction "1_1") (pintype "passive"))
      (node (ref "R8") (pin "2") (pinfunction "2_2") (pintype "passive"))
    )
    (net (code "35") (name "Net-(I2C-Pad3)") (class "Default")
      (node (ref "I2C") (pin "3") (pinfunction "3_3") (pintype "passive"))
      (node (ref "R7") (pin "2") (pinfunction "2_2") (pintype "passive"))
    )
    (net (code "36") (name "Net-(J1-RX)") (class "Default")
      (node (ref "J1") (pin "15") (pinfunction "RX_15") (pintype "bidirectional"))
      (node (ref "R21") (pin "1") (pinfunction "1_1") (pintype "passive"))
    )
    (net (code "37") (name "Net-(J1-~{RESET})") (class "Default")
      (node (ref "J1") (pin "28") (pinfunction "~{RESET}_28") (pintype "bidirectional"))
      (node (ref "JP1") (pin "3") (pinfunction "3_3") (pintype "passive"))
    )
    (net (code "38") (name "Net-(J2-CC1)") (class "Default")
      (node (ref "J2") (pin "A5") (pinfunction "CC1_A5") (pintype "bidirectional"))
      (node (ref "R10") (pin "2") (pinfunction "2_2") (pintype "passive"))
    )
    (net (code "39") (name "Net-(J2-CC2)") (class "Default")
      (node (ref "J2") (pin "B5") (pinfunction "CC2_B5") (pintype "bidirectional"))
      (node (ref "R9") (pin "2") (pinfunction "2_2") (pintype "passive"))
    )
    (net (code "40") (name "Net-(J2-SHLD-PadSHLD1)") (class "Default")
      (node (ref "J2") (pin "SHLD1") (pinfunction "SHLD_SHLD1") (pintype "bidirectional"))
      (node (ref "J2") (pin "SHLD2") (pinfunction "SHLD_SHLD2") (pintype "bidirectional"))
      (node (ref "J2") (pin "SHLD3") (pinfunction "SHLD_SHLD3") (pintype "bidirectional"))
      (node (ref "J2") (pin "SHLD4") (pinfunction "SHLD_SHLD4") (pintype "bidirectional"))
      (node (ref "J2") (pin "SHLD5") (pinfunction "SHLD_SHLD5") (pintype "bidirectional"))
      (node (ref "J2") (pin "SHLD6") (pinfunction "SHLD_SHLD6") (pintype "bidirectional"))
      (node (ref "J2") (pin "SHLD7") (pinfunction "SHLD_SHLD7") (pintype "bidirectional"))
      (node (ref "J2") (pin "SHLD8") (pinfunction "SHLD_SHLD8") (pintype "bidirectional"))
      (node (ref "SHLD") (pin "2") (pinfunction "2_2") (pintype "passive"))
    )
    (net (code "41") (name "Net-(PWR-Pad1)") (class "Default")
      (node (ref "PWR") (pin "1") (pinfunction "1_1") (pintype "passive"))
      (node (ref "R13") (pin "2") (pinfunction "2_2") (pintype "passive"))
    )
    (net (code "42") (name "Net-(Q1-S)") (class "Default")
      (node (ref "D1") (pin "C") (pinfunction "C_C") (pintype "passive"))
      (node (ref "MEAS") (pin "1") (pinfunction "1_1") (pintype "passive"))
      (node (ref "MEAS") (pin "3") (pinfunction "1_3") (pintype "passive"))
      (node (ref "Q1") (pin "2") (pinfunction "S_2") (pintype "bidirectional"))
    )
    (net (code "43") (name "Net-(U2-IN)") (class "Default")
      (node (ref "C13") (pin "1") (pinfunction "1_1") (pintype "passive"))
      (node (ref "MEAS") (pin "2") (pinfunction "2_2") (pintype "passive"))
      (node (ref "MEAS") (pin "4") (pinfunction "2_4") (pintype "passive"))
      (node (ref "R2") (pin "1") (pinfunction "1_1") (pintype "passive"))
      (node (ref "U2") (pin "1") (pinfunction "IN_1") (pintype "input"))
    )
    (net (code "44") (name "Net-(U3A-HFXTAL_N{slash}PB14)") (class "Default")
      (node (ref "U3") (pin "N10") (pinfunction "HFXTAL_N/PB14_N10") (pintype "bidirectional"))
      (node (ref "Y1") (pin "1") (pinfunction "1_1") (pintype "passive"))
    )
    (net (code "45") (name "Net-(U3A-HFXTAL_P{slash}PB13)") (class "Default")
      (node (ref "U3") (pin "N9") (pinfunction "HFXTAL_P/PB13_N9") (pintype "bidirectional"))
      (node (ref "Y1") (pin "3") (pinfunction "2_3") (pintype "passive"))
    )
    (net (code "46") (name "Net-(U3A-PB10)") (class "Default")
      (node (ref "R15") (pin "1") (pinfunction "1_1") (pintype "passive"))
      (node (ref "U3") (pin "L9") (pinfunction "PB10_L9") (pintype "bidirectional"))
    )
    (net (code "47") (name "Net-(U3B-PC2{slash}USART2_TX)") (class "Default")
      (node (ref "R20") (pin "1") (pinfunction "1_1") (pintype "passive"))
      (node (ref "U3") (pin "L1") (pinfunction "PC2/USART2_TX_L1") (pintype "bidirectional"))
    )
    (net (code "48") (name "Net-(U3B-PD0)") (class "Default")
      (node (ref "C3") (pin "1") (pinfunction "1_1") (pintype "passive"))
      (node (ref "R1") (pin "1") (pinfunction "1_1") (pintype "passive"))
      (node (ref "U3") (pin "L10") (pinfunction "PD0_L10") (pintype "bidirectional"))
    )
    (net (code "49") (name "Net-(U3D-DECOUPLE)") (class "Default")
      (node (ref "C7") (pin "1") (pinfunction "1_1") (pintype "passive"))
      (node (ref "U3") (pin "J13") (pinfunction "DECOUPLE_J13") (pintype "bidirectional"))
    )
    (net (code "50") (name "Net-(U4-PROG)") (class "Default")
      (node (ref "CHG_I") (pin "2") (pinfunction "2_2") (pintype "passive"))
      (node (ref "U4") (pin "5") (pinfunction "PROG_5") (pintype "input"))
    )
    (net (code "51") (name "Net-(U4-STAT)") (class "Default")
      (node (ref "D2") (pin "C") (pinfunction "C_C") (pintype "passive"))
      (node (ref "U4") (pin "1") (pinfunction "STAT_1") (pintype "output"))
    )
    (net (code "52") (name "PA00") (class "Default")
      (node (ref "J1") (pin "6") (pinfunction "GPIO3_6") (pintype "bidirectional"))
      (node (ref "U1") (pin "7") (pinfunction "PA00_7") (pintype "bidirectional"))
    )
    (net (code "53") (name "PA04") (class "Default")
      (node (ref "J1") (pin "7") (pinfunction "GPIO2_7") (pintype "bidirectional"))
      (node (ref "U1") (pin "11") (pinfunction "TDI/PA04_11") (pintype "bidirectional"))
    )
    (net (code "54") (name "PB00") (class "Default")
      (node (ref "J1") (pin "5") (pinfunction "GPIO4_5") (pintype "bidirectional"))
      (node (ref "U1") (pin "6") (pinfunction "VDAC0_CH0/PB00_6") (pintype "bidirectional"))
    )
    (net (code "55") (name "PB01") (class "Default")
      (node (ref "J1") (pin "4") (pinfunction "GPIO5_4") (pintype "bidirectional"))
      (node (ref "U1") (pin "5") (pinfunction "VDAC0_CH1/PB01_5") (pintype "bidirectional"))
    )
    (net (code "56") (name "PB02") (class "Default")
      (node (ref "J1") (pin "3") (pinfunction "GPIO6_3") (pintype "bidirectional"))
      (node (ref "U1") (pin "4") (pinfunction "VDAC1_CH0/PB02_4") (pintype "bidirectional"))
    )
    (net (code "57") (name "PC00") (class "Default")
      (node (ref "J1") (pin "20") (pinfunction "A4_20") (pintype "bidirectional"))
      (node (ref "U1") (pin "22") (pinfunction "PC00_22") (pintype "bidirectional"))
    )
    (net (code "58") (name "PC01") (class "Default")
      (node (ref "J1") (pin "19") (pinfunction "A5_19") (pintype "bidirectional"))
      (node (ref "U1") (pin "24") (pinfunction "PC01_24") (pintype "bidirectional"))
    )
    (net (code "59") (name "PC07") (class "Default")
      (node (ref "J1") (pin "13") (pinfunction "FREEBIE_13") (pintype "bidirectional"))
      (node (ref "U1") (pin "30") (pinfunction "PC07_30") (pintype "bidirectional"))
    )
    (net (code "60") (name "PD00") (class "Default")
      (node (ref "J1") (pin "21") (pinfunction "A3_21") (pintype "bidirectional"))
      (node (ref "U1") (pin "21") (pinfunction "PD00_21") (pintype "bidirectional"))
    )
    (net (code "61") (name "PD01") (class "Default")
      (node (ref "J1") (pin "22") (pinfunction "A2_22") (pintype "bidirectional"))
      (node (ref "U1") (pin "20") (pinfunction "PD01_20") (pintype "bidirectional"))
    )
    (net (code "62") (name "PD02") (class "Default")
      (node (ref "J1") (pin "23") (pinfunction "A1_23") (pintype "bidirectional"))
      (node (ref "U1") (pin "19") (pinfunction "PD02_19") (pintype "bidirectional"))
    )
    (net (code "63") (name "PD03") (class "Default")
      (node (ref "D3_ISO") (pin "1") (pinfunction "1_1") (pintype "passive"))
      (node (ref "U1") (pin "18") (pinfunction "PD03_18") (pintype "bidirectional"))
    )
    (net (code "64") (name "PICO{slash}PC03") (class "Default")
      (node (ref "J1") (pin "17") (pinfunction "PICO_17") (pintype "bidirectional"))
      (node (ref "J5") (pin "3") (pinfunction "CMD/SDI_3") (pintype "bidirectional"))
      (node (ref "U1") (pin "26") (pinfunction "PC03_26") (pintype "bidirectional"))
    )
    (net (code "65") (name "POCI{slash}PC06") (class "Default")
      (node (ref "J1") (pin "16") (pinfunction "POCI_16") (pintype "bidirectional"))
      (node (ref "J5") (pin "7") (pinfunction "DAT0/SDO_7") (pintype "bidirectional"))
      (node (ref "U1") (pin "29") (pinfunction "PC06_29") (pintype "bidirectional"))
    )
    (net (code "66") (name "PTI_DATA{slash}PC04") (class "Default")
      (node (ref "J1") (pin "8") (pinfunction "GPIO1_8") (pintype "bidirectional"))
      (node (ref "J7") (pin "10") (pinfunction "10_10") (pintype "passive"))
      (node (ref "U1") (pin "27") (pinfunction "PC04_27") (pintype "bidirectional"))
      (node (ref "U3") (pin "N1") (pinfunction "USART4_RX/PB8_N1") (pintype "bidirectional"))
    )
    (net (code "67") (name "PTI_FRAME{slash}PC05") (class "Default")
      (node (ref "J1") (pin "9") (pinfunction "GPIO0_9") (pintype "bidirectional"))
      (node (ref "J7") (pin "9") (pinfunction "9_9") (pintype "passive"))
      (node (ref "U1") (pin "28") (pinfunction "PC05_28") (pintype "bidirectional"))
      (node (ref "U3") (pin "N2") (pinfunction "PC5/USART4_CS_N2") (pintype "bidirectional"))
    )
    (net (code "68") (name "RX{slash}PA06") (class "Default")
      (node (ref "J7") (pin "4") (pinfunction "4_4") (pintype "passive"))
      (node (ref "R20") (pin "2") (pinfunction "2_2") (pintype "passive"))
      (node (ref "R21") (pin "2") (pinfunction "2_2") (pintype "passive"))
      (node (ref "U1") (pin "13") (pinfunction "PA06_13") (pintype "bidirectional"))
    )
    (net (code "69") (name "SCK{slash}PC02") (class "Default")
      (node (ref "J1") (pin "18") (pinfunction "SCK_18") (pintype "bidirectional"))
      (node (ref "J5") (pin "5") (pinfunction "CLK/SCK_5") (pintype "bidirectional"))
      (node (ref "U1") (pin "25") (pinfunction "PC02_25") (pintype "bidirectional"))
    )
    (net (code "70") (name "SCL{slash}PB03") (class "Default")
      (node (ref "J1") (pin "2") (pinfunction "SCL_2") (pintype "bidirectional"))
      (node (ref "J3") (pin "4") (pinfunction "4_4") (pintype "passive"))
      (node (ref "R7") (pin "1") (pinfunction "1_1") (pintype "passive"))
      (node (ref "U1") (pin "3") (pinfunction "VDAC1_CH1/PB03_3") (pintype "bidirectional"))
      (node (ref "U5") (pin "7") (pinfunction "SCL_7") (pintype "output"))
    )
    (net (code "71") (name "SDA{slash}PB04") (class "Default")
      (node (ref "J1") (pin "1") (pinfunction "SDA_1") (pintype "bidirectional"))
      (node (ref "J3") (pin "3") (pinfunction "3_3") (pintype "passive"))
      (node (ref "R8") (pin "1") (pinfunction "1_1") (pintype "passive"))
      (node (ref "U1") (pin "2") (pinfunction "PB04_2") (pintype "bidirectional"))
      (node (ref "U5") (pin "8") (pinfunction "SDA_8") (pintype "input"))
    )
    (net (code "72") (name "SWCLK{slash}PA01") (class "Default")
      (node (ref "J7") (pin "8") (pinfunction "8_8") (pintype "passive"))
      (node (ref "U1") (pin "8") (pinfunction "TCK/SWCLK/PA01_8") (pintype "bidirectional"))
      (node (ref "U3") (pin "C1") (pinfunction "PA1_C1") (pintype "bidirectional"))
    )
    (net (code "73") (name "SWDIO{slash}PA02") (class "Default")
      (node (ref "J7") (pin "7") (pinfunction "7_7") (pintype "passive"))
      (node (ref "U1") (pin "9") (pinfunction "TMS/SWDIO/PA02_9") (pintype "bidirectional"))
      (node (ref "U3") (pin "C2") (pinfunction "PA0_C2") (pintype "bidirectional"))
      (node (ref "U3") (pin "D3") (pinfunction "PB15_D3") (pintype "bidirectional"))
    )
    (net (code "74") (name "SWO{slash}PA03") (class "Default")
      (node (ref "J7") (pin "6") (pinfunction "6_6") (pintype "passive"))
      (node (ref "U1") (pin "10") (pinfunction "TDO/SWO/PA03_10") (pintype "bidirectional"))
      (node (ref "U3") (pin "E3") (pinfunction "PA4/UART0_RX_E3") (pintype "bidirectional"))
    )
    (net (code "75") (name "TX{slash}PA05") (class "Default")
      (node (ref "J1") (pin "14") (pinfunction "TX_14") (pintype "bidirectional"))
      (node (ref "J7") (pin "5") (pinfunction "5_5") (pintype "passive"))
      (node (ref "U1") (pin "12") (pinfunction "PA05_12") (pintype "bidirectional"))
      (node (ref "U3") (pin "K1") (pinfunction "PC0_K1") (pintype "bidirectional"))
      (node (ref "U3") (pin "L2") (pinfunction "PC3/USART2_RX_L2") (pintype "bidirectional"))
    )
    (net (code "76") (name "USB_N") (class "Default")
      (node (ref "D3") (pin "6") (pinfunction "6_6") (pintype "bidirectional"))
      (node (ref "U3") (pin "B13") (pinfunction "USB_N/PF10_B13") (pintype "bidirectional"))
    )
    (net (code "77") (name "USB_P") (class "Default")
      (node (ref "D3") (pin "4") (pinfunction "4_4") (pintype "bidirectional"))
      (node (ref "U3") (pin "A13") (pinfunction "USB_P/PF11_A13") (pintype "bidirectional"))
    )
    (net (code "78") (name "V_BATT") (class "Default")
      (node (ref "C16") (pin "1") (pinfunction "1_1") (pintype "passive"))
      (node (ref "C17") (pin "1") (pinfunction "1_1") (pintype "passive"))
      (node (ref "J1") (pin "12") (pinfunction "V_BATT_12") (pintype "bidirectional"))
      (node (ref "J4") (pin "2") (pinfunction "+_2") (pintype "bidirectional"))
      (node (ref "Q1") (pin "3") (pinfunction "D_3") (pintype "bidirectional"))
      (node (ref "U4") (pin "3") (pinfunction "VBAT_3") (pintype "power_in"))
      (node (ref "U5") (pin "2") (pinfunction "CELL_2") (pintype "input"))
      (node (ref "U5") (pin "3") (pinfunction "VDD_3") (pintype "bidirectional"))
    )
    (net (code "79") (name "V_USB") (class "Default")
      (node (ref "C11") (pin "1") (pinfunction "1_1") (pintype "passive"))
      (node (ref "C15") (pin "1") (pinfunction "1_1") (pintype "passive"))
      (node (ref "D1") (pin "A") (pinfunction "A_A") (pintype "passive"))
      (node (ref "D3") (pin "5") (pinfunction "5_5") (pintype "power_in"))
      (node (ref "J1") (pin "10") (pinfunction "V_USB_10") (pintype "bidirectional"))
      (node (ref "J2") (pin "VBUS1") (pinfunction "VBUS_VBUS1") (pintype "bidirectional"))
      (node (ref "J2") (pin "VBUS2") (pinfunction "VBUS_VBUS2") (pintype "bidirectional"))
      (node (ref "LP") (pin "2") (pinfunction "2_2") (pintype "passive"))
      (node (ref "Q1") (pin "1") (pinfunction "G_1") (pintype "bidirectional"))
      (node (ref "R3") (pin "2") (pinfunction "2_2") (pintype "passive"))
      (node (ref "R4") (pin "2") (pinfunction "2_2") (pintype "passive"))
      (node (ref "U3") (pin "A11") (pinfunction "VREGI_A11") (pintype "bidirectional"))
      (node (ref "U3") (pin "B12") (pinfunction "VBUS_B12") (pintype "bidirectional"))
      (node (ref "U4") (pin "4") (pinfunction "VIN_4") (pintype "power_in"))
    )
    (net (code "80") (name "unconnected-(J1-AREF{slash}NC-Pad26)") (class "Default")
      (node (ref "J1") (pin "26") (pinfunction "AREF/NC_26") (pintype "bidirectional"))
    )
    (net (code "81") (name "unconnected-(J4-PAD1-PadNC1)") (class "Default")
      (node (ref "J4") (pin "NC1") (pinfunction "PAD1_NC1") (pintype "bidirectional"))
    )
    (net (code "82") (name "unconnected-(J4-PAD2-PadNC2)") (class "Default")
      (node (ref "J4") (pin "NC2") (pinfunction "PAD2_NC2") (pintype "bidirectional"))
    )
    (net (code "83") (name "unconnected-(J5-DAT1-Pad8)") (class "Default")
      (node (ref "J5") (pin "8") (pinfunction "DAT1_8") (pintype "bidirectional"))
    )
    (net (code "84") (name "unconnected-(J5-DAT2-Pad1)") (class "Default")
      (node (ref "J5") (pin "1") (pinfunction "DAT2_1") (pintype "bidirectional"))
    )
    (net (code "85") (name "unconnected-(J5-DET-Pad9)") (class "Default")
      (node (ref "J5") (pin "9") (pinfunction "DET_9") (pintype "bidirectional"))
    )
    (net (code "86") (name "unconnected-(U1-RFOUT-Pad33)") (class "Default")
      (node (ref "U1") (pin "33") (pinfunction "RFOUT_33") (pintype "output"))
    )
    (net (code "87") (name "unconnected-(U3A-PA2-PadD2)") (class "Default")
      (node (ref "U3") (pin "D2") (pinfunction "PA2_D2") (pintype "bidirectional"))
    )
    (net (code "88") (name "unconnected-(U3A-PA5-PadE2)") (class "Default")
      (node (ref "U3") (pin "E2") (pinfunction "PA5_E2") (pintype "bidirectional"))
    )
    (net (code "89") (name "unconnected-(U3A-PA7-PadL3)") (class "Default")
      (node (ref "U3") (pin "L3") (pinfunction "PA7_L3") (pintype "bidirectional"))
    )
    (net (code "90") (name "unconnected-(U3A-PA8-PadM3)") (class "Default")
      (node (ref "U3") (pin "M3") (pinfunction "PA8_M3") (pintype "bidirectional"))
    )
    (net (code "91") (name "unconnected-(U3A-PA9-PadN3)") (class "Default")
      (node (ref "U3") (pin "N3") (pinfunction "PA9_N3") (pintype "bidirectional"))
    )
    (net (code "92") (name "unconnected-(U3A-PA10-PadM4)") (class "Default")
      (node (ref "U3") (pin "M4") (pinfunction "PA10_M4") (pintype "bidirectional"))
    )
    (net (code "93") (name "unconnected-(U3A-PA11-PadN4)") (class "Default")
      (node (ref "U3") (pin "N4") (pinfunction "PA11_N4") (pintype "bidirectional"))
    )
    (net (code "94") (name "unconnected-(U3A-PA12-PadN5)") (class "Default")
      (node (ref "U3") (pin "N5") (pinfunction "PA12_N5") (pintype "bidirectional"))
    )
    (net (code "95") (name "unconnected-(U3A-PA13-PadM5)") (class "Default")
      (node (ref "U3") (pin "M5") (pinfunction "PA13_M5") (pintype "bidirectional"))
    )
    (net (code "96") (name "unconnected-(U3A-PA14-PadM6)") (class "Default")
      (node (ref "U3") (pin "M6") (pinfunction "PA14_M6") (pintype "bidirectional"))
    )
    (net (code "97") (name "unconnected-(U3A-PB0-PadF1)") (class "Default")
      (node (ref "U3") (pin "F1") (pinfunction "PB0_F1") (pintype "bidirectional"))
    )
    (net (code "98") (name "unconnected-(U3A-PB1-PadF2)") (class "Default")
      (node (ref "U3") (pin "F2") (pinfunction "PB1_F2") (pintype "bidirectional"))
    )
    (net (code "99") (name "unconnected-(U3A-PB2-PadF3)") (class "Default")
      (node (ref "U3") (pin "F3") (pinfunction "PB2_F3") (pintype "bidirectional"))
    )
    (net (code "100") (name "unconnected-(U3A-PB3-PadG1)") (class "Default")
      (node (ref "U3") (pin "G1") (pinfunction "PB3_G1") (pintype "bidirectional"))
    )
    (net (code "101") (name "unconnected-(U3A-PB4-PadG2)") (class "Default")
      (node (ref "U3") (pin "G2") (pinfunction "PB4_G2") (pintype "bidirectional"))
    )
    (net (code "102") (name "unconnected-(U3A-PB5-PadH1)") (class "Default")
      (node (ref "U3") (pin "H1") (pinfunction "PB5_H1") (pintype "bidirectional"))
    )
    (net (code "103") (name "unconnected-(U3A-PB6-PadH2)") (class "Default")
      (node (ref "U3") (pin "H2") (pinfunction "PB6_H2") (pintype "bidirectional"))
    )
    (net (code "104") (name "unconnected-(U3A-PB7-PadM1)") (class "Default")
      (node (ref "U3") (pin "M1") (pinfunction "PB7_M1") (pintype "bidirectional"))
    )
    (net (code "105") (name "unconnected-(U3A-PB11-PadN6)") (class "Default")
      (node (ref "U3") (pin "N6") (pinfunction "PB11_N6") (pintype "bidirectional"))
    )
    (net (code "106") (name "unconnected-(U3A-PB12-PadN7)") (class "Default")
      (node (ref "U3") (pin "N7") (pinfunction "PB12_N7") (pintype "bidirectional"))
    )
    (net (code "107") (name "unconnected-(U3B-PC1-PadK2)") (class "Default")
      (node (ref "U3") (pin "K2") (pinfunction "PC1_K2") (pintype "bidirectional"))
    )
    (net (code "108") (name "unconnected-(U3B-PC4{slash}USART4_CLK-PadM2)") (class "Default")
      (node (ref "U3") (pin "M2") (pinfunction "PC4/USART4_CLK_M2") (pintype "bidirectional"))
    )
    (net (code "109") (name "unconnected-(U3B-PC8-PadF12)") (class "Default")
      (node (ref "U3") (pin "F12") (pinfunction "PC8_F12") (pintype "bidirectional"))
    )
    (net (code "110") (name "unconnected-(U3B-PC10-PadE12)") (class "Default")
      (node (ref "U3") (pin "E12") (pinfunction "PC10_E12") (pintype "bidirectional"))
    )
    (net (code "111") (name "unconnected-(U3B-PC11-PadE13)") (class "Default")
      (node (ref "U3") (pin "E13") (pinfunction "PC11_E13") (pintype "bidirectional"))
    )
    (net (code "112") (name "unconnected-(U3B-PC12{slash}USART2_CTS-PadD12)") (class "Default")
      (node (ref "U3") (pin "D12") (pinfunction "PC12/USART2_CTS_D12") (pintype "bidirectional"))
    )
    (net (code "113") (name "unconnected-(U3B-PC13-PadD13)") (class "Default")
      (node (ref "U3") (pin "D13") (pinfunction "PC13_D13") (pintype "bidirectional"))
    )
    (net (code "114") (name "unconnected-(U3B-PC14{slash}USART_RTS-PadC12)") (class "Default")
      (node (ref "U3") (pin "C12") (pinfunction "PC14/USART_RTS_C12") (pintype "bidirectional"))
    )
    (net (code "115") (name "unconnected-(U3B-PC15-PadC13)") (class "Default")
      (node (ref "U3") (pin "C13") (pinfunction "PC15_C13") (pintype "bidirectional"))
    )
    (net (code "116") (name "unconnected-(U3B-PD1-PadL11)") (class "Default")
      (node (ref "U3") (pin "L11") (pinfunction "PD1_L11") (pintype "bidirectional"))
    )
    (net (code "117") (name "unconnected-(U3B-PD3-PadM12)") (class "Default")
      (node (ref "U3") (pin "M12") (pinfunction "PD3_M12") (pintype "bidirectional"))
    )
    (net (code "118") (name "unconnected-(U3B-PD4-PadL12)") (class "Default")
      (node (ref "U3") (pin "L12") (pinfunction "PD4_L12") (pintype "bidirectional"))
    )
    (net (code "119") (name "unconnected-(U3B-PD5-PadN13)") (class "Default")
      (node (ref "U3") (pin "N13") (pinfunction "PD5_N13") (pintype "bidirectional"))
    )
    (net (code "120") (name "unconnected-(U3B-PD6-PadM13)") (class "Default")
      (node (ref "U3") (pin "M13") (pinfunction "PD6_M13") (pintype "bidirectional"))
    )
    (net (code "121") (name "unconnected-(U3B-PD7-PadL13)") (class "Default")
      (node (ref "U3") (pin "L13") (pinfunction "PD7_L13") (pintype "bidirectional"))
    )
    (net (code "122") (name "unconnected-(U3B-PD8-PadK13)") (class "Default")
      (node (ref "U3") (pin "K13") (pinfunction "PD8_K13") (pintype "bidirectional"))
    )
    (net (code "123") (name "unconnected-(U3B-PD9-PadA6)") (class "Default")
      (node (ref "U3") (pin "A6") (pinfunction "PD9_A6") (pintype "bidirectional"))
    )
    (net (code "124") (name "unconnected-(U3B-PD10-PadB6)") (class "Default")
      (node (ref "U3") (pin "B6") (pinfunction "PD10_B6") (pintype "bidirectional"))
    )
    (net (code "125") (name "unconnected-(U3B-PD11-PadA5)") (class "Default")
      (node (ref "U3") (pin "A5") (pinfunction "PD11_A5") (pintype "bidirectional"))
    )
    (net (code "126") (name "unconnected-(U3B-PD12-PadB5)") (class "Default")
      (node (ref "U3") (pin "B5") (pinfunction "PD12_B5") (pintype "bidirectional"))
    )
    (net (code "127") (name "unconnected-(U3B-PD13-PadC4)") (class "Default")
      (node (ref "U3") (pin "C4") (pinfunction "PD13_C4") (pintype "bidirectional"))
    )
    (net (code "128") (name "unconnected-(U3B-PD14-PadJ1)") (class "Default")
      (node (ref "U3") (pin "J1") (pinfunction "PD14_J1") (pintype "bidirectional"))
    )
    (net (code "129") (name "unconnected-(U3B-PD15-PadJ2)") (class "Default")
      (node (ref "U3") (pin "J2") (pinfunction "PD15_J2") (pintype "bidirectional"))
    )
    (net (code "130") (name "unconnected-(U3C-PE0-PadG11)") (class "Default")
      (node (ref "U3") (pin "G11") (pinfunction "PE0_G11") (pintype "bidirectional"))
    )
    (net (code "131") (name "unconnected-(U3C-PE1-PadG12)") (class "Default")
      (node (ref "U3") (pin "G12") (pinfunction "PE1_G12") (pintype "bidirectional"))
    )
    (net (code "132") (name "unconnected-(U3C-PE4-PadC11)") (class "Default")
      (node (ref "U3") (pin "C11") (pinfunction "PE4_C11") (pintype "bidirectional"))
    )
    (net (code "133") (name "unconnected-(U3C-PE5-PadD11)") (class "Default")
      (node (ref "U3") (pin "D11") (pinfunction "PE5_D11") (pintype "bidirectional"))
    )
    (net (code "134") (name "unconnected-(U3C-PE6-PadE11)") (class "Default")
      (node (ref "U3") (pin "E11") (pinfunction "PE6_E11") (pintype "bidirectional"))
    )
    (net (code "135") (name "unconnected-(U3C-PE7-PadF11)") (class "Default")
      (node (ref "U3") (pin "F11") (pinfunction "PE7_F11") (pintype "bidirectional"))
    )
    (net (code "136") (name "unconnected-(U3C-PE8-PadB4)") (class "Default")
      (node (ref "U3") (pin "B4") (pinfunction "PE8_B4") (pintype "bidirectional"))
    )
    (net (code "137") (name "unconnected-(U3C-PF3-PadB9)") (class "Default")
      (node (ref "U3") (pin "B9") (pinfunction "PF3_B9") (pintype "bidirectional"))
    )
    (net (code "138") (name "unconnected-(U3C-PF5-PadA8)") (class "Default")
      (node (ref "U3") (pin "A8") (pinfunction "PF5_A8") (pintype "bidirectional"))
    )
    (net (code "139") (name "unconnected-(U3C-PF6-PadB8)") (class "Default")
      (node (ref "U3") (pin "B8") (pinfunction "PF6_B8") (pintype "bidirectional"))
    )
    (net (code "140") (name "unconnected-(U3C-PF7-PadA7)") (class "Default")
      (node (ref "U3") (pin "A7") (pinfunction "PF7_A7") (pintype "bidirectional"))
    )
    (net (code "141") (name "unconnected-(U3C-PF8-PadB7)") (class "Default")
      (node (ref "U3") (pin "B7") (pinfunction "PF8_B7") (pintype "bidirectional"))
    )
    (net (code "142") (name "unconnected-(U3C-PF9-PadC7)") (class "Default")
      (node (ref "U3") (pin "C7") (pinfunction "PF9_C7") (pintype "bidirectional"))
    )
    (net (code "143") (name "unconnected-(U3C-USB_ID{slash}PF12-PadB11)") (class "Default")
      (node (ref "U3") (pin "B11") (pinfunction "USB_ID/PF12_B11") (pintype "bidirectional"))
    )
    (net (code "144") (name "unconnected-(U5-~{ALRT}-Pad5)") (class "Default")
      (node (ref "U5") (pin "5") (pinfunction "~{ALRT}_5") (pintype "bidirectional"))
    )
    (net (code "145") (name "unconnected-(U7-~{RESET}-Pad7)") (class "Default")
      (node (ref "U7") (pin "7") (pinfunction "~{RESET}_7") (pintype "bidirectional"))
    )
  )
)
